# esquematico.net
KiCad netlist of a schematic drawn in Altium Designer
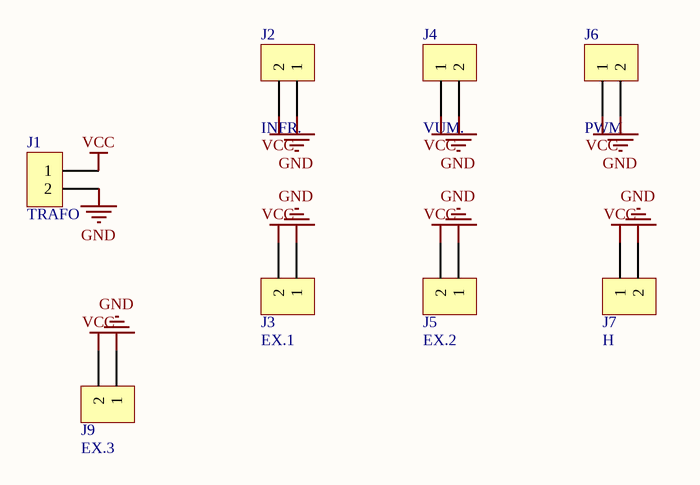
[diagram p0: esquematico.SchDoc]

(export (version "E")
  (design (tool "Eeschema 10.0.6"))
  (components
    (comp (ref "J1") (value "TRAFO") (footprint "BORNERA2") (libsource (lib "") (part "BORNERA 2_3")))
    (comp (ref "J2") (value "INFR.") (footprint "BORNERA2") (libsource (lib "") (part "BORNERA 2_2")))
    (comp (ref "J3") (value "EX.1") (footprint "BORNERA2") (libsource (lib "") (part "BORNERA 2_1")))
    (comp (ref "J4") (value "VUM.") (footprint "BORNERA2") (libsource (lib "") (part "BORNERA 2_4")))
    (comp (ref "J5") (value "EX.2") (footprint "BORNERA2") (libsource (lib "") (part "BORNERA 2_1")))
    (comp (ref "J6") (value "PWM") (footprint "BORNERA2") (libsource (lib "") (part "BORNERA 2_4")))
    (comp (ref "J7") (value "H") (footprint "BORNERA2") (libsource (lib "Schematics") (part "BORNERA 2")))
    (comp (ref "J9") (value "EX.3") (footprint "BORNERA2") (libsource (lib "") (part "BORNERA 2_1")))
  )
  (nets
    (net (code "1") (name "GND") (class "Default")
      (node (ref "J1") (pin "2") (pinfunction "2_2") (pintype "passive"))
      (node (ref "J2") (pin "1") (pinfunction "1_1") (pintype "passive"))
      (node (ref "J3") (pin "1") (pinfunction "1_1") (pintype "passive"))
      (node (ref "J4") (pin "2") (pinfunction "2_2") (pintype "passive"))
      (node (ref "J5") (pin "1") (pinfunction "1_1") (pintype "passive"))
      (node (ref "J6") (pin "2") (pinfunction "2_2") (pintype "passive"))
      (node (ref "J7") (pin "2") (pinfunction "2_2") (pintype "passive"))
      (node (ref "J9") (pin "1") (pinfunction "1_1") (pintype "passive"))
    )
    (net (code "2") (name "VCC") (class "Default")
      (node (ref "J1") (pin "1") (pinfunction "1_1") (pintype "passive"))
      (node (ref "J2") (pin "2") (pinfunction "2_2") (pintype "passive"))
      (node (ref "J3") (pin "2") (pinfunction "2_2") (pintype "passive"))
      (node (ref "J4") (pin "1") (pinfunction "1_1") (pintype "passive"))
      (node (ref "J5") (pin "2") (pinfunction "2_2") (pintype "passive"))
      (node (ref "J6") (pin "1") (pinfunction "1_1") (pintype "passive"))
      (node (ref "J7") (pin "1") (pinfunction "1_1") (pintype "passive"))
      (node (ref "J9") (pin "2") (pinfunction "2_2") (pintype "passive"))
    )
  )
)
